# DAC_SUPPLY.net
KiCad netlist of a schematic drawn in Altium Designer
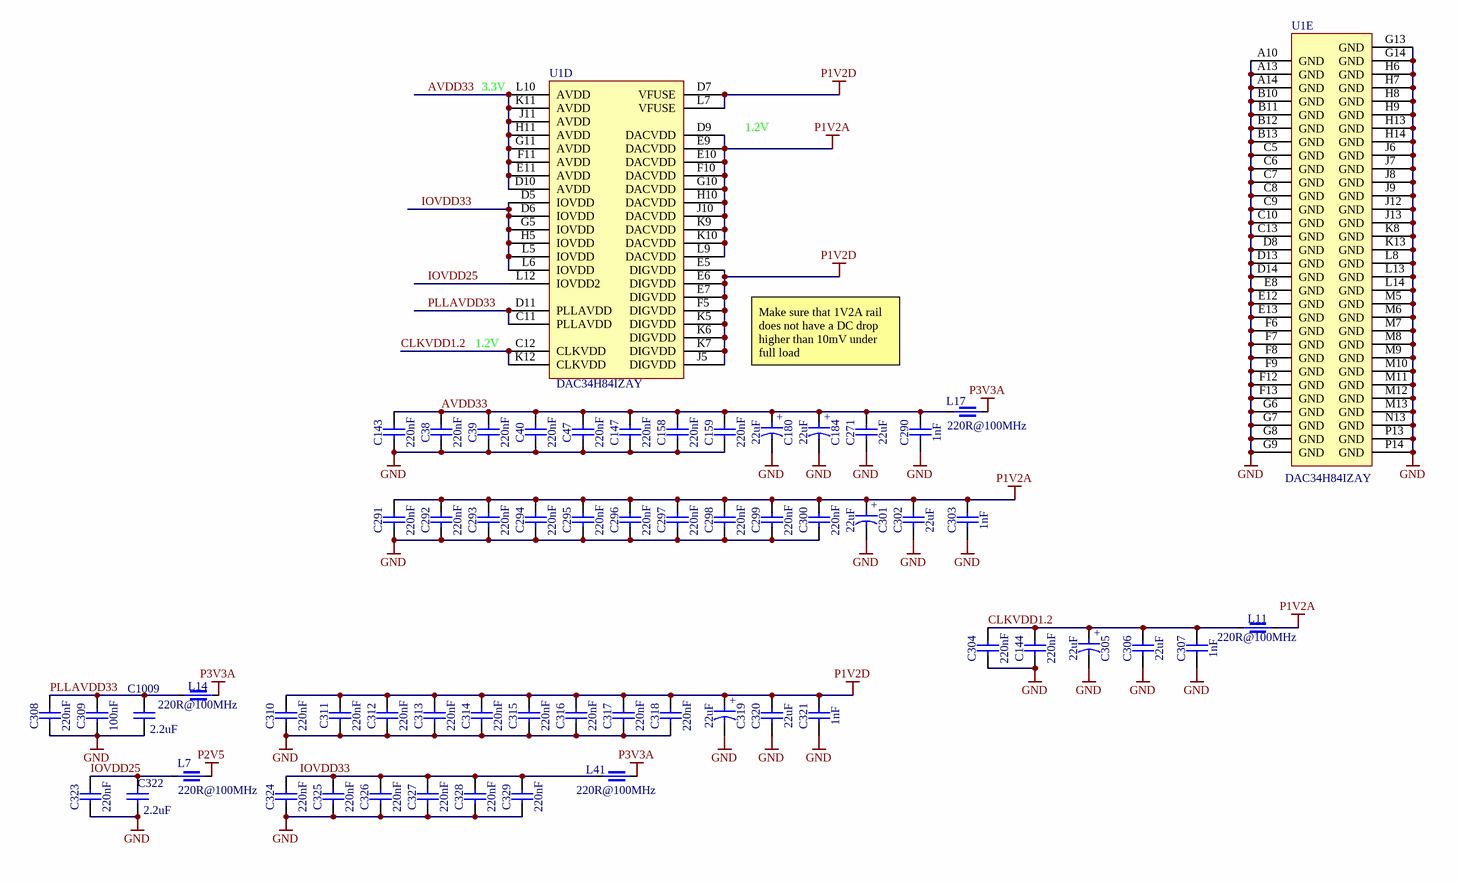
[diagram p0: DAC_SUPPLY.SchDoc]

(export (version "E")
  (design (tool "Eeschema 10.0.6"))
  (components
    (comp (ref "C38")
      (value "220nF")
      (footprint "CAPC0603X33N")
      (description "Non-polarised capacitor")
      (fields
        (field (name "PART NUMBER") "CC0201_220NF_6.3V_20%_X5R")
        (field (name "VOLTAGE") "6.3V")
        (field (name "AUTHOR") "CERN DEM JLC")
      )
      (libsource (lib "Capacitors") (part "Capacitor - non polarized"))
    )
    (comp (ref "C39")
      (value "220nF")
      (footprint "CAPC0603X33N")
      (description "Non-polarised capacitor")
      (fields
        (field (name "PART NUMBER") "CC0201_220NF_6.3V_20%_X5R")
        (field (name "VOLTAGE") "6.3V")
        (field (name "AUTHOR") "CERN DEM JLC")
      )
      (libsource (lib "Capacitors") (part "Capacitor - non polarized"))
    )
    (comp (ref "C40")
      (value "220nF")
      (footprint "CAPC0603X33N")
      (description "Non-polarised capacitor")
      (fields
        (field (name "PART NUMBER") "CC0201_220NF_6.3V_20%_X5R")
        (field (name "VOLTAGE") "6.3V")
        (field (name "AUTHOR") "CERN DEM JLC")
      )
      (libsource (lib "Capacitors") (part "Capacitor - non polarized"))
    )
    (comp (ref "C47")
      (value "220nF")
      (footprint "CAPC0603X33N")
      (description "Non-polarised capacitor")
      (fields
        (field (name "PART NUMBER") "CC0201_220NF_6.3V_20%_X5R")
        (field (name "VOLTAGE") "6.3V")
        (field (name "AUTHOR") "CERN DEM JLC")
      )
      (libsource (lib "Capacitors") (part "Capacitor - non polarized"))
    )
    (comp (ref "C143")
      (value "220nF")
      (footprint "CAPC0603X33N")
      (description "Non-polarised capacitor")
      (fields
        (field (name "PART NUMBER") "CC0201_220NF_6.3V_20%_X5R")
        (field (name "VOLTAGE") "6.3V")
        (field (name "AUTHOR") "CERN DEM JLC")
      )
      (libsource (lib "Capacitors") (part "Capacitor - non polarized"))
    )
    (comp (ref "C144")
      (value "220nF")
      (footprint "CAPC0603X33N")
      (description "Non-polarised capacitor")
      (fields
        (field (name "PART NUMBER") "CC0201_220NF_6.3V_20%_X5R")
        (field (name "VOLTAGE") "6.3V")
        (field (name "AUTHOR") "CERN DEM JLC")
      )
      (libsource (lib "Capacitors") (part "Capacitor - non polarized"))
    )
    (comp (ref "C147")
      (value "220nF")
      (footprint "CAPC0603X33N")
      (description "Non-polarised capacitor")
      (fields
        (field (name "PART NUMBER") "CC0201_220NF_6.3V_20%_X5R")
        (field (name "VOLTAGE") "6.3V")
        (field (name "AUTHOR") "CERN DEM JLC")
      )
      (libsource (lib "Capacitors") (part "Capacitor - non polarized"))
    )
    (comp (ref "C158")
      (value "220nF")
      (footprint "CAPC0603X33N")
      (description "Non-polarised capacitor")
      (fields
        (field (name "PART NUMBER") "CC0201_220NF_6.3V_20%_X5R")
        (field (name "VOLTAGE") "6.3V")
        (field (name "AUTHOR") "CERN DEM JLC")
      )
      (libsource (lib "Capacitors") (part "Capacitor - non polarized"))
    )
    (comp (ref "C159")
      (value "220nF")
      (footprint "CAPC0603X33N")
      (description "Non-polarised capacitor")
      (fields
        (field (name "PART NUMBER") "CC0201_220NF_6.3V_20%_X5R")
        (field (name "VOLTAGE") "6.3V")
        (field (name "AUTHOR") "CERN DEM JLC")
      )
      (libsource (lib "Capacitors") (part "Capacitor - non polarized"))
    )
    (comp (ref "C180")
      (value "22uF")
      (footprint "CAPMP3528X210N")
      (description "Polarised capacitor")
      (fields
        (field (name "PART NUMBER") "CTE3528-21_22UF_10V_10%_LESR0700")
        (field (name "VOLTAGE") "10V")
        (field (name "AUTHOR") "CERN DEM JLC")
      )
      (libsource (lib "Capacitors") (part "Capacitor - polarized"))
    )
    (comp (ref "C184")
      (value "22uF")
      (footprint "CAPMP3528X210N")
      (description "Polarised capacitor")
      (fields
        (field (name "PART NUMBER") "CTE3528-21_22UF_10V_10%_LESR0700")
        (field (name "VOLTAGE") "10V")
        (field (name "AUTHOR") "CERN DEM JLC")
      )
      (libsource (lib "Capacitors") (part "Capacitor - polarized"))
    )
    (comp (ref "C271")
      (value "22uF")
      (footprint "CAPC1709X100N")
      (description "Non-polarised capacitor")
      (fields
        (field (name "PART NUMBER") "CC0603_22UF_6.3V_20%_X5R")
        (field (name "VOLTAGE") "6.3V")
        (field (name "AUTHOR") "CERN DEM JLC")
      )
      (libsource (lib "Capacitors") (part "Capacitor - non polarized"))
    )
    (comp (ref "C290")
      (value "1nF")
      (footprint "CAPC1005X55N")
      (description "Non-polarised capacitor")
      (fields
        (field (name "PART NUMBER") "CC0402_1NF_50V_10%_X7R")
        (field (name "VOLTAGE") "50V")
        (field (name "AUTHOR") "CERN DEM JLC")
      )
      (libsource (lib "Capacitors") (part "Capacitor - non polarized"))
    )
    (comp (ref "C291")
      (value "220nF")
      (footprint "CAPC0603X33N")
      (description "Non-polarised capacitor")
      (fields
        (field (name "PART NUMBER") "CC0201_220NF_6.3V_20%_X5R")
        (field (name "VOLTAGE") "6.3V")
        (field (name "AUTHOR") "CERN DEM JLC")
      )
      (libsource (lib "Capacitors") (part "Capacitor - non polarized"))
    )
    (comp (ref "C292")
      (value "220nF")
      (footprint "CAPC0603X33N")
      (description "Non-polarised capacitor")
      (fields
        (field (name "PART NUMBER") "CC0201_220NF_6.3V_20%_X5R")
        (field (name "VOLTAGE") "6.3V")
        (field (name "AUTHOR") "CERN DEM JLC")
      )
      (libsource (lib "Capacitors") (part "Capacitor - non polarized"))
    )
    (comp (ref "C293")
      (value "220nF")
      (footprint "CAPC0603X33N")
      (description "Non-polarised capacitor")
      (fields
        (field (name "PART NUMBER") "CC0201_220NF_6.3V_20%_X5R")
        (field (name "VOLTAGE") "6.3V")
        (field (name "AUTHOR") "CERN DEM JLC")
      )
      (libsource (lib "Capacitors") (part "Capacitor - non polarized"))
    )
    (comp (ref "C294")
      (value "220nF")
      (footprint "CAPC0603X33N")
      (description "Non-polarised capacitor")
      (fields
        (field (name "PART NUMBER") "CC0201_220NF_6.3V_20%_X5R")
        (field (name "VOLTAGE") "6.3V")
        (field (name "AUTHOR") "CERN DEM JLC")
      )
      (libsource (lib "Capacitors") (part "Capacitor - non polarized"))
    )
    (comp (ref "C295")
      (value "220nF")
      (footprint "CAPC0603X33N")
      (description "Non-polarised capacitor")
      (fields
        (field (name "PART NUMBER") "CC0201_220NF_6.3V_20%_X5R")
        (field (name "VOLTAGE") "6.3V")
        (field (name "AUTHOR") "CERN DEM JLC")
      )
      (libsource (lib "Capacitors") (part "Capacitor - non polarized"))
    )
    (comp (ref "C296")
      (value "220nF")
      (footprint "CAPC0603X33N")
      (description "Non-polarised capacitor")
      (fields
        (field (name "PART NUMBER") "CC0201_220NF_6.3V_20%_X5R")
        (field (name "VOLTAGE") "6.3V")
        (field (name "AUTHOR") "CERN DEM JLC")
      )
      (libsource (lib "Capacitors") (part "Capacitor - non polarized"))
    )
    (comp (ref "C297")
      (value "220nF")
      (footprint "CAPC0603X33N")
      (description "Non-polarised capacitor")
      (fields
        (field (name "PART NUMBER") "CC0201_220NF_6.3V_20%_X5R")
        (field (name "VOLTAGE") "6.3V")
        (field (name "AUTHOR") "CERN DEM JLC")
      )
      (libsource (lib "Capacitors") (part "Capacitor - non polarized"))
    )
    (comp (ref "C298")
      (value "220nF")
      (footprint "CAPC0603X33N")
      (description "Non-polarised capacitor")
      (fields
        (field (name "PART NUMBER") "CC0201_220NF_6.3V_20%_X5R")
        (field (name "VOLTAGE") "6.3V")
        (field (name "AUTHOR") "CERN DEM JLC")
      )
      (libsource (lib "Capacitors") (part "Capacitor - non polarized"))
    )
    (comp (ref "C299")
      (value "220nF")
      (footprint "CAPC0603X33N")
      (description "Non-polarised capacitor")
      (fields
        (field (name "PART NUMBER") "CC0201_220NF_6.3V_20%_X5R")
        (field (name "VOLTAGE") "6.3V")
        (field (name "AUTHOR") "CERN DEM JLC")
      )
      (libsource (lib "Capacitors") (part "Capacitor - non polarized"))
    )
    (comp (ref "C300")
      (value "220nF")
      (footprint "CAPC0603X33N")
      (description "Non-polarised capacitor")
      (fields
        (field (name "PART NUMBER") "CC0201_220NF_6.3V_20%_X5R")
        (field (name "VOLTAGE") "6.3V")
        (field (name "AUTHOR") "CERN DEM JLC")
      )
      (libsource (lib "Capacitors") (part "Capacitor - non polarized"))
    )
    (comp (ref "C301")
      (value "22uF")
      (footprint "CAPMP3528X210N")
      (description "Polarised capacitor")
      (fields
        (field (name "PART NUMBER") "CTE3528-21_22UF_10V_10%_LESR0700")
        (field (name "VOLTAGE") "10V")
        (field (name "AUTHOR") "CERN DEM JLC")
      )
      (libsource (lib "Capacitors") (part "Capacitor - polarized"))
    )
    (comp (ref "C302")
      (value "22uF")
      (footprint "CAPC1709X100N")
      (description "Non-polarised capacitor")
      (fields
        (field (name "PART NUMBER") "CC0603_22UF_6.3V_20%_X5R")
        (field (name "VOLTAGE") "6.3V")
        (field (name "AUTHOR") "CERN DEM JLC")
      )
      (libsource (lib "Capacitors") (part "Capacitor - non polarized"))
    )
    (comp (ref "C303")
      (value "1nF")
      (footprint "CAPC1005X55N")
      (description "Non-polarised capacitor")
      (fields
        (field (name "PART NUMBER") "CC0402_1NF_50V_10%_X7R")
        (field (name "VOLTAGE") "50V")
        (field (name "AUTHOR") "CERN DEM JLC")
      )
      (libsource (lib "Capacitors") (part "Capacitor - non polarized"))
    )
    (comp (ref "C304")
      (value "220nF")
      (footprint "CAPC0603X33N")
      (description "Non-polarised capacitor")
      (fields
        (field (name "PART NUMBER") "CC0201_220NF_6.3V_20%_X5R")
        (field (name "VOLTAGE") "6.3V")
        (field (name "AUTHOR") "CERN DEM JLC")
      )
      (libsource (lib "Capacitors") (part "Capacitor - non polarized"))
    )
    (comp (ref "C305")
      (value "22uF")
      (footprint "CAPMP3528X210N")
      (description "Polarised capacitor")
      (fields
        (field (name "PART NUMBER") "CTE3528-21_22UF_10V_10%_LESR0700")
        (field (name "VOLTAGE") "10V")
        (field (name "AUTHOR") "CERN DEM JLC")
      )
      (libsource (lib "Capacitors") (part "Capacitor - polarized"))
    )
    (comp (ref "C306")
      (value "22uF")
      (footprint "CAPC1709X100N")
      (description "Non-polarised capacitor")
      (fields
        (field (name "PART NUMBER") "CC0603_22UF_6.3V_20%_X5R")
        (field (name "VOLTAGE") "6.3V")
        (field (name "AUTHOR") "CERN DEM JLC")
      )
      (libsource (lib "Capacitors") (part "Capacitor - non polarized"))
    )
    (comp (ref "C307")
      (value "1nF")
      (footprint "CAPC1005X55N")
      (description "Non-polarised capacitor")
      (fields
        (field (name "PART NUMBER") "CC0402_1NF_50V_10%_X7R")
        (field (name "VOLTAGE") "50V")
        (field (name "AUTHOR") "CERN DEM JLC")
      )
      (libsource (lib "Capacitors") (part "Capacitor - non polarized"))
    )
    (comp (ref "C308")
      (value "220nF")
      (footprint "CAPC0603X33N")
      (description "Non-polarised capacitor")
      (fields
        (field (name "PART NUMBER") "CC0201_220NF_6.3V_20%_X5R")
        (field (name "VOLTAGE") "6.3V")
        (field (name "AUTHOR") "CERN DEM JLC")
      )
      (libsource (lib "Capacitors") (part "Capacitor - non polarized"))
    )
    (comp (ref "C309")
      (value "100nF")
      (footprint "CAPC1608X90N")
      (description "Non-polarised capacitor")
      (fields
        (field (name "PART NUMBER") "CC0603_100NF_100V_10%_X7R")
        (field (name "VOLTAGE") "100V")
        (field (name "AUTHOR") "CERN DEM JLC")
      )
      (libsource (lib "Capacitors") (part "Capacitor - non polarized"))
    )
    (comp (ref "C310")
      (value "220nF")
      (footprint "CAPC0603X33N")
      (description "Non-polarised capacitor")
      (fields
        (field (name "PART NUMBER") "CC0201_220NF_6.3V_20%_X5R")
        (field (name "VOLTAGE") "6.3V")
        (field (name "AUTHOR") "CERN DEM JLC")
      )
      (libsource (lib "Capacitors") (part "Capacitor - non polarized"))
    )
    (comp (ref "C311")
      (value "220nF")
      (footprint "CAPC0603X33N")
      (description "Non-polarised capacitor")
      (fields
        (field (name "PART NUMBER") "CC0201_220NF_6.3V_20%_X5R")
        (field (name "VOLTAGE") "6.3V")
        (field (name "AUTHOR") "CERN DEM JLC")
      )
      (libsource (lib "Capacitors") (part "Capacitor - non polarized"))
    )
    (comp (ref "C312")
      (value "220nF")
      (footprint "CAPC0603X33N")
      (description "Non-polarised capacitor")
      (fields
        (field (name "PART NUMBER") "CC0201_220NF_6.3V_20%_X5R")
        (field (name "VOLTAGE") "6.3V")
        (field (name "AUTHOR") "CERN DEM JLC")
      )
      (libsource (lib "Capacitors") (part "Capacitor - non polarized"))
    )
    (comp (ref "C313")
      (value "220nF")
      (footprint "CAPC0603X33N")
      (description "Non-polarised capacitor")
      (fields
        (field (name "PART NUMBER") "CC0201_220NF_6.3V_20%_X5R")
        (field (name "VOLTAGE") "6.3V")
        (field (name "AUTHOR") "CERN DEM JLC")
      )
      (libsource (lib "Capacitors") (part "Capacitor - non polarized"))
    )
    (comp (ref "C314")
      (value "220nF")
      (footprint "CAPC0603X33N")
      (description "Non-polarised capacitor")
      (fields
        (field (name "PART NUMBER") "CC0201_220NF_6.3V_20%_X5R")
        (field (name "VOLTAGE") "6.3V")
        (field (name "AUTHOR") "CERN DEM JLC")
      )
      (libsource (lib "Capacitors") (part "Capacitor - non polarized"))
    )
    (comp (ref "C315")
      (value "220nF")
      (footprint "CAPC0603X33N")
      (description "Non-polarised capacitor")
      (fields
        (field (name "PART NUMBER") "CC0201_220NF_6.3V_20%_X5R")
        (field (name "VOLTAGE") "6.3V")
        (field (name "AUTHOR") "CERN DEM JLC")
      )
      (libsource (lib "Capacitors") (part "Capacitor - non polarized"))
    )
    (comp (ref "C316")
      (value "220nF")
      (footprint "CAPC0603X33N")
      (description "Non-polarised capacitor")
      (fields
        (field (name "PART NUMBER") "CC0201_220NF_6.3V_20%_X5R")
        (field (name "VOLTAGE") "6.3V")
        (field (name "AUTHOR") "CERN DEM JLC")
      )
      (libsource (lib "Capacitors") (part "Capacitor - non polarized"))
    )
    (comp (ref "C317")
      (value "220nF")
      (footprint "CAPC0603X33N")
      (description "Non-polarised capacitor")
      (fields
        (field (name "PART NUMBER") "CC0201_220NF_6.3V_20%_X5R")
        (field (name "VOLTAGE") "6.3V")
        (field (name "AUTHOR") "CERN DEM JLC")
      )
      (libsource (lib "Capacitors") (part "Capacitor - non polarized"))
    )
    (comp (ref "C318")
      (value "220nF")
      (footprint "CAPC0603X33N")
      (description "Non-polarised capacitor")
      (fields
        (field (name "PART NUMBER") "CC0201_220NF_6.3V_20%_X5R")
        (field (name "VOLTAGE") "6.3V")
        (field (name "AUTHOR") "CERN DEM JLC")
      )
      (libsource (lib "Capacitors") (part "Capacitor - non polarized"))
    )
    (comp (ref "C319")
      (value "22uF")
      (footprint "CAPMP3528X210N")
      (description "Polarised capacitor")
      (fields
        (field (name "PART NUMBER") "CTE3528-21_22UF_10V_10%_LESR0700")
        (field (name "VOLTAGE") "10V")
        (field (name "AUTHOR") "CERN DEM JLC")
      )
      (libsource (lib "Capacitors") (part "Capacitor - polarized"))
    )
    (comp (ref "C320")
      (value "22uF")
      (footprint "CAPC1709X100N")
      (description "Non-polarised capacitor")
      (fields
        (field (name "PART NUMBER") "CC0603_22UF_6.3V_20%_X5R")
        (field (name "VOLTAGE") "6.3V")
        (field (name "AUTHOR") "CERN DEM JLC")
      )
      (libsource (lib "Capacitors") (part "Capacitor - non polarized"))
    )
    (comp (ref "C321")
      (value "1nF")
      (footprint "CAPC1005X55N")
      (description "Non-polarised capacitor")
      (fields
        (field (name "PART NUMBER") "CC0402_1NF_50V_10%_X7R")
        (field (name "VOLTAGE") "50V")
        (field (name "AUTHOR") "CERN DEM JLC")
      )
      (libsource (lib "Capacitors") (part "Capacitor - non polarized"))
    )
    (comp (ref "C322")
      (value "2.2uF")
      (footprint "CAPC1005X55N")
      (description "Non-polarised capacitor")
      (fields
        (field (name "PART NUMBER") "CC0402_2.2UF_6.3V_10%_X5R")
        (field (name "VOLTAGE") "6.3V")
        (field (name "AUTHOR") "CERN DEM JMW")
      )
      (libsource (lib "Capacitors") (part "Capacitor - non polarized"))
    )
    (comp (ref "C323")
      (value "220nF")
      (footprint "CAPC0603X33N")
      (description "Non-polarised capacitor")
      (fields
        (field (name "PART NUMBER") "CC0201_220NF_6.3V_20%_X5R")
        (field (name "VOLTAGE") "6.3V")
        (field (name "AUTHOR") "CERN DEM JLC")
      )
      (libsource (lib "Capacitors") (part "Capacitor - non polarized"))
    )
    (comp (ref "C324")
      (value "220nF")
      (footprint "CAPC0603X33N")
      (description "Non-polarised capacitor")
      (fields
        (field (name "PART NUMBER") "CC0201_220NF_6.3V_20%_X5R")
        (field (name "VOLTAGE") "6.3V")
        (field (name "AUTHOR") "CERN DEM JLC")
      )
      (libsource (lib "Capacitors") (part "Capacitor - non polarized"))
    )
    (comp (ref "C325")
      (value "220nF")
      (footprint "CAPC0603X33N")
      (description "Non-polarised capacitor")
      (fields
        (field (name "PART NUMBER") "CC0201_220NF_6.3V_20%_X5R")
        (field (name "VOLTAGE") "6.3V")
        (field (name "AUTHOR") "CERN DEM JLC")
      )
      (libsource (lib "Capacitors") (part "Capacitor - non polarized"))
    )
    (comp (ref "C326")
      (value "220nF")
      (footprint "CAPC0603X33N")
      (description "Non-polarised capacitor")
      (fields
        (field (name "PART NUMBER") "CC0201_220NF_6.3V_20%_X5R")
        (field (name "VOLTAGE") "6.3V")
        (field (name "AUTHOR") "CERN DEM JLC")
      )
      (libsource (lib "Capacitors") (part "Capacitor - non polarized"))
    )
    (comp (ref "C327")
      (value "220nF")
      (footprint "CAPC0603X33N")
      (description "Non-polarised capacitor")
      (fields
        (field (name "PART NUMBER") "CC0201_220NF_6.3V_20%_X5R")
        (field (name "VOLTAGE") "6.3V")
        (field (name "AUTHOR") "CERN DEM JLC")
      )
      (libsource (lib "Capacitors") (part "Capacitor - non polarized"))
    )
    (comp (ref "C328")
      (value "220nF")
      (footprint "CAPC0603X33N")
      (description "Non-polarised capacitor")
      (fields
        (field (name "PART NUMBER") "CC0201_220NF_6.3V_20%_X5R")
        (field (name "VOLTAGE") "6.3V")
        (field (name "AUTHOR") "CERN DEM JLC")
      )
      (libsource (lib "Capacitors") (part "Capacitor - non polarized"))
    )
    (comp (ref "C329")
      (value "220nF")
      (footprint "CAPC0603X33N")
      (description "Non-polarised capacitor")
      (fields
        (field (name "PART NUMBER") "CC0201_220NF_6.3V_20%_X5R")
        (field (name "VOLTAGE") "6.3V")
        (field (name "AUTHOR") "CERN DEM JLC")
      )
      (libsource (lib "Capacitors") (part "Capacitor - non polarized"))
    )
    (comp (ref "C1009")
      (value "2.2uF")
      (footprint "CAPC1005X55N")
      (description "Non-polarised capacitor")
      (fields
        (field (name "PART NUMBER") "CC0402_2.2UF_6.3V_10%_X5R")
        (field (name "VOLTAGE") "6.3V")
        (field (name "AUTHOR") "CERN DEM JMW")
      )
      (libsource (lib "Capacitors") (part "Capacitor - non polarized"))
    )
    (comp (ref "L7")
      (value "220R@100MHz")
      (footprint "INDC1608X95N")
      (fields
        (field (name "PART NUMBER") "IND0603_MURATA_BLM18SG221TN1")
        (field (name "POWER") "2.5A")
        (field (name "TOLERANCE") "±25%")
        (field (name "AUTHOR") "CERN DEM MR")
      )
      (libsource (lib "Inductors & Transformers") (part "Ferrite Bead"))
    )
    (comp (ref "L11")
      (value "220R@100MHz")
      (footprint "INDC1608X95N")
      (fields
        (field (name "PART NUMBER") "IND0603_MURATA_BLM18SG221TN1")
        (field (name "POWER") "2.5A")
        (field (name "TOLERANCE") "±25%")
        (field (name "AUTHOR") "CERN DEM MR")
      )
      (libsource (lib "Inductors & Transformers") (part "Ferrite Bead"))
    )
    (comp (ref "L14")
      (value "220R@100MHz")
      (footprint "INDC1608X95N")
      (fields
        (field (name "PART NUMBER") "IND0603_MURATA_BLM18SG221TN1")
        (field (name "POWER") "2.5A")
        (field (name "TOLERANCE") "±25%")
        (field (name "AUTHOR") "CERN DEM MR")
      )
      (libsource (lib "Inductors & Transformers") (part "Ferrite Bead"))
    )
    (comp (ref "L17")
      (value "220R@100MHz")
      (footprint "INDC1608X95N")
      (fields
        (field (name "PART NUMBER") "IND0603_MURATA_BLM18SG221TN1")
        (field (name "POWER") "2.5A")
        (field (name "TOLERANCE") "±25%")
        (field (name "AUTHOR") "CERN DEM MR")
      )
      (libsource (lib "Inductors & Transformers") (part "Ferrite Bead"))
    )
    (comp (ref "L41")
      (value "220R@100MHz")
      (footprint "INDC1608X95N")
      (fields
        (field (name "PART NUMBER") "IND0603_MURATA_BLM18SG221TN1")
        (field (name "POWER") "2.5A")
        (field (name "TOLERANCE") "±25%")
        (field (name "AUTHOR") "CERN DEM MR")
      )
      (libsource (lib "Inductors & Transformers") (part "Ferrite Bead"))
    )
    (comp (ref "U1")
      (value "DAC34H84IZAY")
      (footprint "TI-ZAY196")
      (description "Quad-Channel, 16-Bit, 1.5 GSPS DAC, -40 to 85 degC, 196-pin BGA (ZAY196), Green (RoHS & no Sb/Br)")
      (fields (field (name "MANUFACTURER") "Texas Instruments"))
      (libsource (lib "Altium Content Vault") (part "TI-DAC34H_SH84-ZAY196"))
    )
  )
  (nets
    (net (code "1") (name "/AVDD33") (class "Default")
      (node (ref "C143") (pin "2") (pinfunction "2_2") (pintype "passive"))
      (node (ref "C147") (pin "2") (pinfunction "2_2") (pintype "passive"))
      (node (ref "C158") (pin "2") (pinfunction "2_2") (pintype "passive"))
      (node (ref "C159") (pin "2") (pinfunction "2_2") (pintype "passive"))
      (node (ref "C180") (pin "1") (pinfunction "1_1") (pintype "passive"))
      (node (ref "C184") (pin "1") (pinfunction "1_1") (pintype "passive"))
      (node (ref "C271") (pin "2") (pinfunction "2_2") (pintype "passive"))
      (node (ref "C290") (pin "2") (pinfunction "2_2") (pintype "passive"))
      (node (ref "C38") (pin "2") (pinfunction "2_2") (pintype "passive"))
      (node (ref "C39") (pin "2") (pinfunction "2_2") (pintype "passive"))
      (node (ref "C40") (pin "2") (pinfunction "2_2") (pintype "passive"))
      (node (ref "C47") (pin "2") (pinfunction "2_2") (pintype "passive"))
      (node (ref "L17") (pin "1") (pinfunction "1_1") (pintype "passive"))
      (node (ref "U1") (pin "D10") (pinfunction "AVDD_D10") (pintype "power_in"))
      (node (ref "U1") (pin "E11") (pinfunction "AVDD_E11") (pintype "power_in"))
      (node (ref "U1") (pin "F11") (pinfunction "AVDD_F11") (pintype "power_in"))
      (node (ref "U1") (pin "G11") (pinfunction "AVDD_G11") (pintype "power_in"))
      (node (ref "U1") (pin "H11") (pinfunction "AVDD_H11") (pintype "power_in"))
      (node (ref "U1") (pin "J11") (pinfunction "AVDD_J11") (pintype "power_in"))
      (node (ref "U1") (pin "K11") (pinfunction "AVDD_K11") (pintype "power_in"))
      (node (ref "U1") (pin "L10") (pinfunction "AVDD_L10") (pintype "power_in"))
    )
    (net (code "2") (name "/CLKVDD1.2") (class "Default")
      (node (ref "C144") (pin "2") (pinfunction "2_2") (pintype "passive"))
      (node (ref "C304") (pin "2") (pinfunction "2_2") (pintype "passive"))
      (node (ref "C305") (pin "1") (pinfunction "1_1") (pintype "passive"))
      (node (ref "C306") (pin "2") (pinfunction "2_2") (pintype "passive"))
      (node (ref "C307") (pin "2") (pinfunction "2_2") (pintype "passive"))
      (node (ref "L11") (pin "1") (pinfunction "1_1") (pintype "passive"))
      (node (ref "U1") (pin "C12") (pinfunction "CLKVDD_C12") (pintype "power_in"))
      (node (ref "U1") (pin "K12") (pinfunction "CLKVDD_K12") (pintype "power_in"))
    )
    (net (code "3") (name "/IOVDD25") (class "Default")
      (node (ref "C322") (pin "2") (pinfunction "2_2") (pintype "passive"))
      (node (ref "C323") (pin "2") (pinfunction "2_2") (pintype "passive"))
      (node (ref "L7") (pin "1") (pinfunction "1_1") (pintype "passive"))
      (node (ref "U1") (pin "L12") (pinfunction "IOVDD2_L12") (pintype "power_in"))
    )
    (net (code "4") (name "/IOVDD33") (class "Default")
      (node (ref "C324") (pin "2") (pinfunction "2_2") (pintype "passive"))
      (node (ref "C325") (pin "2") (pinfunction "2_2") (pintype "passive"))
      (node (ref "C326") (pin "2") (pinfunction "2_2") (pintype "passive"))
      (node (ref "C327") (pin "2") (pinfunction "2_2") (pintype "passive"))
      (node (ref "C328") (pin "2") (pinfunction "2_2") (pintype "passive"))
      (node (ref "C329") (pin "2") (pinfunction "2_2") (pintype "passive"))
      (node (ref "L41") (pin "1") (pinfunction "1_1") (pintype "passive"))
      (node (ref "U1") (pin "D5") (pinfunction "IOVDD_D5") (pintype "power_in"))
      (node (ref "U1") (pin "D6") (pinfunction "IOVDD_D6") (pintype "power_in"))
      (node (ref "U1") (pin "G5") (pinfunction "IOVDD_G5") (pintype "power_in"))
      (node (ref "U1") (pin "H5") (pinfunction "IOVDD_H5") (pintype "power_in"))
      (node (ref "U1") (pin "L5") (pinfunction "IOVDD_L5") (pintype "power_in"))
      (node (ref "U1") (pin "L6") (pinfunction "IOVDD_L6") (pintype "power_in"))
    )
    (net (code "5") (name "/PLLAVDD33") (class "Default")
      (node (ref "C1009") (pin "2") (pinfunction "2_2") (pintype "passive"))
      (node (ref "C308") (pin "2") (pinfunction "2_2") (pintype "passive"))
      (node (ref "C309") (pin "2") (pinfunction "2_2") (pintype "passive"))
      (node (ref "L14") (pin "1") (pinfunction "1_1") (pintype "passive"))
      (node (ref "U1") (pin "C11") (pinfunction "PLLAVDD_C11") (pintype "power_in"))
      (node (ref "U1") (pin "D11") (pinfunction "PLLAVDD_D11") (pintype "power_in"))
    )
    (net (code "6") (name "GND") (class "Default")
      (node (ref "C1009") (pin "1") (pinfunction "1_1") (pintype "passive"))
      (node (ref "C143") (pin "1") (pinfunction "1_1") (pintype "passive"))
      (node (ref "C144") (pin "1") (pinfunction "1_1") (pintype "passive"))
      (node (ref "C147") (pin "1") (pinfunction "1_1") (pintype "passive"))
      (node (ref "C158") (pin "1") (pinfunction "1_1") (pintype "passive"))
      (node (ref "C159") (pin "1") (pinfunction "1_1") (pintype "passive"))
      (node (ref "C180") (pin "2") (pinfunction "2_2") (pintype "passive"))
      (node (ref "C184") (pin "2") (pinfunction "2_2") (pintype "passive"))
      (node (ref "C271") (pin "1") (pinfunction "1_1") (pintype "passive"))
      (node (ref "C290") (pin "1") (pinfunction "1_1") (pintype "passive"))
      (node (ref "C291") (pin "1") (pinfunction "1_1") (pintype "passive"))
      (node (ref "C292") (pin "1") (pinfunction "1_1") (pintype "passive"))
      (node (ref "C293") (pin "1") (pinfunction "1_1") (pintype "passive"))
      (node (ref "C294") (pin "1") (pinfunction "1_1") (pintype "passive"))
      (node (ref "C295") (pin "1") (pinfunction "1_1") (pintype "passive"))
      (node (ref "C296") (pin "1") (pinfunction "1_1") (pintype "passive"))
      (node (ref "C297") (pin "1") (pinfunction "1_1") (pintype "passive"))
      (node (ref "C298") (pin "1") (pinfunction "1_1") (pintype "passive"))
      (node (ref "C299") (pin "1") (pinfunction "1_1") (pintype "passive"))
      (node (ref "C300") (pin "1") (pinfunction "1_1") (pintype "passive"))
      (node (ref "C301") (pin "2") (pinfunction "2_2") (pintype "passive"))
      (node (ref "C302") (pin "1") (pinfunction "1_1") (pintype "passive"))
      (node (ref "C303") (pin "1") (pinfunction "1_1") (pintype "passive"))
      (node (ref "C304") (pin "1") (pinfunction "1_1") (pintype "passive"))
      (node (ref "C305") (pin "2") (pinfunction "2_2") (pintype "passive"))
      (node (ref "C306") (pin "1") (pinfunction "1_1") (pintype "passive"))
      (node (ref "C307") (pin "1") (pinfunction "1_1") (pintype "passive"))
      (node (ref "C308") (pin "1") (pinfunction "1_1") (pintype "passive"))
      (node (ref "C309") (pin "1") (pinfunction "1_1") (pintype "passive"))
      (node (ref "C310") (pin "1") (pinfunction "1_1") (pintype "passive"))
      (node (ref "C311") (pin "1") (pinfunction "1_1") (pintype "passive"))
      (node (ref "C312") (pin "1") (pinfunction "1_1") (pintype "passive"))
      (node (ref "C313") (pin "1") (pinfunction "1_1") (pintype "passive"))
      (node (ref "C314") (pin "1") (pinfunction "1_1") (pintype "passive"))
      (node (ref "C315") (pin "1") (pinfunction "1_1") (pintype "passive"))
      (node (ref "C316") (pin "1") (pinfunction "1_1") (pintype "passive"))
      (node (ref "C317") (pin "1") (pinfunction "1_1") (pintype "passive"))
      (node (ref "C318") (pin "1") (pinfunction "1_1") (pintype "passive"))
      (node (ref "C319") (pin "2") (pinfunction "2_2") (pintype "passive"))
      (node (ref "C320") (pin "1") (pinfunction "1_1") (pintype "passive"))
      (node (ref "C321") (pin "1") (pinfunction "1_1") (pintype "passive"))
      (node (ref "C322") (pin "1") (pinfunction "1_1") (pintype "passive"))
      (node (ref "C323") (pin "1") (pinfunction "1_1") (pintype "passive"))
      (node (ref "C324") (pin "1") (pinfunction "1_1") (pintype "passive"))
      (node (ref "C325") (pin "1") (pinfunction "1_1") (pintype "passive"))
      (node (ref "C326") (pin "1") (pinfunction "1_1") (pintype "passive"))
      (node (ref "C327") (pin "1") (pinfunction "1_1") (pintype "passive"))
      (node (ref "C328") (pin "1") (pinfunction "1_1") (pintype "passive"))
      (node (ref "C329") (pin "1") (pinfunction "1_1") (pintype "passive"))
      (node (ref "C38") (pin "1") (pinfunction "1_1") (pintype "passive"))
      (node (ref "C39") (pin "1") (pinfunction "1_1") (pintype "passive"))
      (node (ref "C40") (pin "1") (pinfunction "1_1") (pintype "passive"))
      (node (ref "C47") (pin "1") (pinfunction "1_1") (pintype "passive"))
      (node (ref "U1") (pin "A10") (pinfunction "GND_A10") (pintype "power_in"))
      (node (ref "U1") (pin "A13") (pinfunction "GND_A13") (pintype "power_in"))
      (node (ref "U1") (pin "A14") (pinfunction "GND_A14") (pintype "power_in"))
      (node (ref "U1") (pin "B10") (pinfunction "GND_B10") (pintype "power_in"))
      (node (ref "U1") (pin "B11") (pinfunction "GND_B11") (pintype "power_in"))
      (node (ref "U1") (pin "B12") (pinfunction "GND_B12") (pintype "power_in"))
      (node (ref "U1") (pin "B13") (pinfunction "GND_B13") (pintype "power_in"))
      (node (ref "U1") (pin "C10") (pinfunction "GND_C10") (pintype "power_in"))
      (node (ref "U1") (pin "C13") (pinfunction "GND_C13") (pintype "power_in"))
      (node (ref "U1") (pin "C5") (pinfunction "GND_C5") (pintype "power_in"))
      (node (ref "U1") (pin "C6") (pinfunction "GND_C6") (pintype "power_in"))
      (node (ref "U1") (pin "C7") (pinfunction "GND_C7") (pintype "power_in"))
      (node (ref "U1") (pin "C8") (pinfunction "GND_C8") (pintype "power_in"))
      (node (ref "U1") (pin "C9") (pinfunction "GND_C9") (pintype "power_in"))
      (node (ref "U1") (pin "D13") (pinfunction "GND_D13") (pintype "power_in"))
      (node (ref "U1") (pin "D14") (pinfunction "GND_D14") (pintype "power_in"))
      (node (ref "U1") (pin "D8") (pinfunction "GND_D8") (pintype "power_in"))
      (node (ref "U1") (pin "E12") (pinfunction "GND_E12") (pintype "power_in"))
      (node (ref "U1") (pin "E13") (pinfunction "GND_E13") (pintype "power_in"))
      (node (ref "U1") (pin "E8") (pinfunction "GND_E8") (pintype "power_in"))
      (node (ref "U1") (pin "F12") (pinfunction "GND_F12") (pintype "power_in"))
      (node (ref "U1") (pin "F13") (pinfunction "GND_F13") (pintype "power_in"))
      (node (ref "U1") (pin "F6") (pinfunction "GND_F6") (pintype "power_in"))
      (node (ref "U1") (pin "F7") (pinfunction "GND_F7") (pintype "power_in"))
      (node (ref "U1") (pin "F8") (pinfunction "GND_F8") (pintype "power_in"))
      (node (ref "U1") (pin "F9") (pinfunction "GND_F9") (pintype "power_in"))
      (node (ref "U1") (pin "G13") (pinfunction "GND_G13") (pintype "power_in"))
      (node (ref "U1") (pin "G14") (pinfunction "GND_G14") (pintype "power_in"))
      (node (ref "U1") (pin "G6") (pinfunction "GND_G6") (pintype "power_in"))
      (node (ref "U1") (pin "G7") (pinfunction "GND_G7") (pintype "power_in"))
      (node (ref "U1") (pin "G8") (pinfunction "GND_G8") (pintype "power_in"))
      (node (ref "U1") (pin "G9") (pinfunction "GND_G9") (pintype "power_in"))
      (node (ref "U1") (pin "H13") (pinfunction "GND_H13") (pintype "power_in"))
      (node (ref "U1") (pin "H14") (pinfunction "GND_H14") (pintype "power_in"))
      (node (ref "U1") (pin "H6") (pinfunction "GND_H6") (pintype "power_in"))
      (node (ref "U1") (pin "H7") (pinfunction "GND_H7") (pintype "power_in"))
      (node (ref "U1") (pin "H8") (pinfunction "GND_H8") (pintype "power_in"))
      (node (ref "U1") (pin "H9") (pinfunction "GND_H9") (pintype "power_in"))
      (node (ref "U1") (pin "J12") (pinfunction "GND_J12") (pintype "power_in"))
      (node (ref "U1") (pin "J13") (pinfunction "GND_J13") (pintype "power_in"))
      (node (ref "U1") (pin "J6") (pinfunction "GND_J6") (pintype "power_in"))
      (node (ref "U1") (pin "J7") (pinfunction "GND_J7") (pintype "power_in"))
      (node (ref "U1") (pin "J8") (pinfunction "GND_J8") (pintype "power_in"))
      (node (ref "U1") (pin "J9") (pinfunction "GND_J9") (pintype "power_in"))
      (node (ref "U1") (pin "K13") (pinfunction "GND_K13") (pintype "power_in"))
      (node (ref "U1") (pin "K8") (pinfunction "GND_K8") (pintype "power_in"))
      (node (ref "U1") (pin "L13") (pinfunction "GND_L13") (pintype "power_in"))
      (node (ref "U1") (pin "L14") (pinfunction "GND_L14") (pintype "power_in"))
      (node (ref "U1") (pin "L8") (pinfunction "GND_L8") (pintype "power_in"))
      (node (ref "U1") (pin "M10") (pinfunction "GND_M10") (pintype "power_in"))
      (node (ref "U1") (pin "M11") (pinfunction "GND_M11") (pintype "power_in"))
      (node (ref "U1") (pin "M12") (pinfunction "GND_M12") (pintype "power_in"))
      (node (ref "U1") (pin "M13") (pinfunction "GND_M13") (pintype "power_in"))
      (node (ref "U1") (pin "M5") (pinfunction "GND_M5") (pintype "power_in"))
      (node (ref "U1") (pin "M6") (pinfunction "GND_M6") (pintype "power_in"))
      (node (ref "U1") (pin "M7") (pinfunction "GND_M7") (pintype "power_in"))
      (node (ref "U1") (pin "M8") (pinfunction "GND_M8") (pintype "power_in"))
      (node (ref "U1") (pin "M9") (pinfunction "GND_M9") (pintype "power_in"))
      (node (ref "U1") (pin "N13") (pinfunction "GND_N13") (pintype "power_in"))
      (node (ref "U1") (pin "P13") (pinfunction "GND_P13") (pintype "power_in"))
      (node (ref "U1") (pin "P14") (pinfunction "GND_P14") (pintype "power_in"))
    )
    (net (code "7") (name "P1V2A") (class "Default")
      (node (ref "C291") (pin "2") (pinfunction "2_2") (pintype "passive"))
      (node (ref "C292") (pin "2") (pinfunction "2_2") (pintype "passive"))
      (node (ref "C293") (pin "2") (pinfunction "2_2") (pintype "passive"))
      (node (ref "C294") (pin "2") (pinfunction "2_2") (pintype "passive"))
      (node (ref "C295") (pin "2") (pinfunction "2_2") (pintype "passive"))
      (node (ref "C296") (pin "2") (pinfunction "2_2") (pintype "passive"))
      (node (ref "C297") (pin "2") (pinfunction "2_2") (pintype "passive"))
      (node (ref "C298") (pin "2") (pinfunction "2_2") (pintype "passive"))
      (node (ref "C299") (pin "2") (pinfunction "2_2") (pintype "passive"))
      (node (ref "C300") (pin "2") (pinfunction "2_2") (pintype "passive"))
      (node (ref "C301") (pin "1") (pinfunction "1_1") (pintype "passive"))
      (node (ref "C302") (pin "2") (pinfunction "2_2") (pintype "passive"))
      (node (ref "C303") (pin "2") (pinfunction "2_2") (pintype "passive"))
      (node (ref "L11") (pin "2") (pinfunction "2_2") (pintype "passive"))
      (node (ref "U1") (pin "D9") (pinfunction "DACVDD_D9") (pintype "power_in"))
      (node (ref "U1") (pin "E10") (pinfunction "DACVDD_E10") (pintype "power_in"))
      (node (ref "U1") (pin "E9") (pinfunction "DACVDD_E9") (pintype "power_in"))
      (node (ref "U1") (pin "F10") (pinfunction "DACVDD_F10") (pintype "power_in"))
      (node (ref "U1") (pin "G10") (pinfunction "DACVDD_G10") (pintype "power_in"))
      (node (ref "U1") (pin "H10") (pinfunction "DACVDD_H10") (pintype "power_in"))
      (node (ref "U1") (pin "J10") (pinfunction "DACVDD_J10") (pintype "power_in"))
      (node (ref "U1") (pin "K10") (pinfunction "DACVDD_K10") (pintype "power_in"))
      (node (ref "U1") (pin "K9") (pinfunction "DACVDD_K9") (pintype "power_in"))
      (node (ref "U1") (pin "L9") (pinfunction "DACVDD_L9") (pintype "power_in"))
    )
    (net (code "8") (name "P1V2D") (class "Default")
      (node (ref "C310") (pin "2") (pinfunction "2_2") (pintype "passive"))
      (node (ref "C311") (pin "2") (pinfunction "2_2") (pintype "passive"))
      (node (ref "C312") (pin "2") (pinfunction "2_2") (pintype "passive"))
      (node (ref "C313") (pin "2") (pinfunction "2_2") (pintype "passive"))
      (node (ref "C314") (pin "2") (pinfunction "2_2") (pintype "passive"))
      (node (ref "C315") (pin "2") (pinfunction "2_2") (pintype "passive"))
      (node (ref "C316") (pin "2") (pinfunction "2_2") (pintype "passive"))
      (node (ref "C317") (pin "2") (pinfunction "2_2") (pintype "passive"))
      (node (ref "C318") (pin "2") (pinfunction "2_2") (pintype "passive"))
      (node (ref "C319") (pin "1") (pinfunction "1_1") (pintype "passive"))
      (node (ref "C320") (pin "2") (pinfunction "2_2") (pintype "passive"))
      (node (ref "C321") (pin "2") (pinfunction "2_2") (pintype "passive"))
      (node (ref "U1") (pin "D7") (pinfunction "VFUSE_D7") (pintype "power_in"))
      (node (ref "U1") (pin "E5") (pinfunction "DIGVDD_E5") (pintype "power_in"))
      (node (ref "U1") (pin "E6") (pinfunction "DIGVDD_E6") (pintype "power_in"))
      (node (ref "U1") (pin "E7") (pinfunction "DIGVDD_E7") (pintype "power_in"))
      (node (ref "U1") (pin "F5") (pinfunction "DIGVDD_F5") (pintype "power_in"))
      (node (ref "U1") (pin "J5") (pinfunction "DIGVDD_J5") (pintype "power_in"))
      (node (ref "U1") (pin "K5") (pinfunction "DIGVDD_K5") (pintype "power_in"))
      (node (ref "U1") (pin "K6") (pinfunction "DIGVDD_K6") (pintype "power_in"))
      (node (ref "U1") (pin "K7") (pinfunction "DIGVDD_K7") (pintype "power_in"))
      (node (ref "U1") (pin "L7") (pinfunction "VFUSE_L7") (pintype "power_in"))
    )
    (net (code "9") (name "P2V5") (class "Default")
      (node (ref "L7") (pin "2") (pinfunction "2_2") (pintype "passive"))
    )
    (net (code "10") (name "P3V3A") (class "Default")
      (node (ref "L14") (pin "2") (pinfunction "2_2") (pintype "passive"))
      (node (ref "L17") (pin "2") (pinfunction "2_2") (pintype "passive"))
      (node (ref "L41") (pin "2") (pinfunction "2_2") (pintype "passive"))
    )
  )
)
